# VOLTAGE_PEAK_V3.net
KiCad netlist of a schematic drawn in Altium Designer
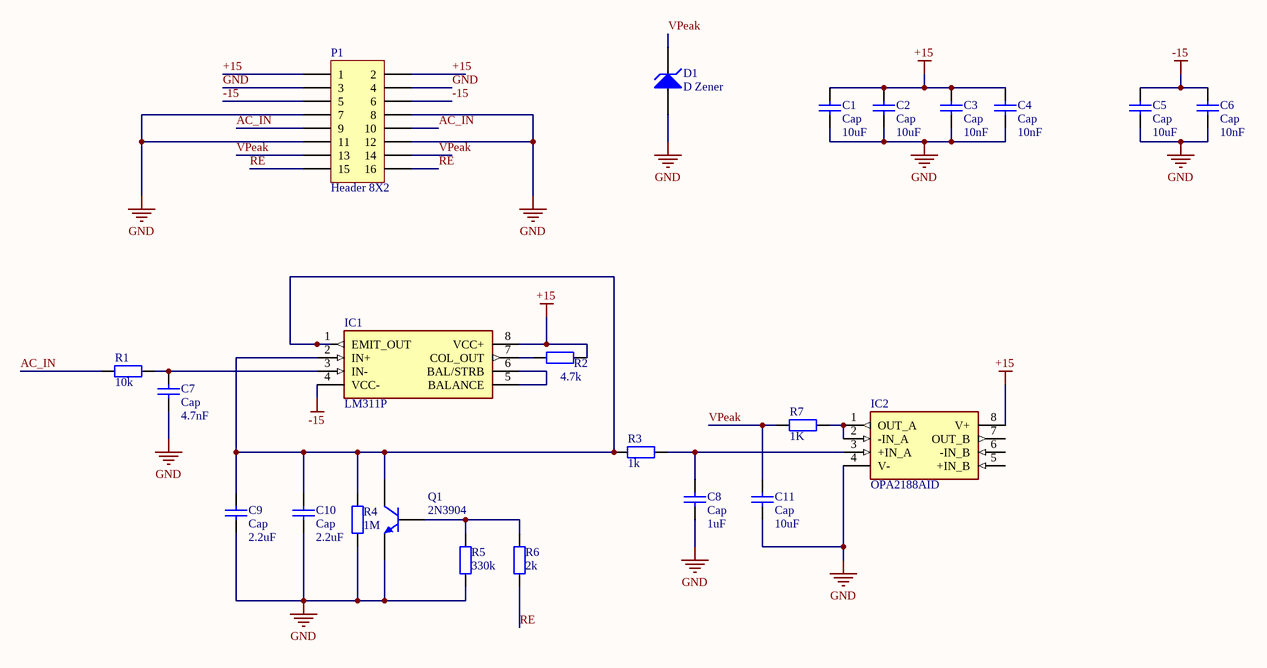
[diagram p0: VOLTAGE_PEAK_V3.SchDoc]

(export (version "E")
  (design (tool "Eeschema 10.0.6"))
  (components
    (comp (ref "C1")
      (value "Cap")
      (footprint "C0805")
      (description "Capacitor")
      (fields (field (name "ALTIUM_VALUE") "10uF") (field (name "PUBLISHER") "Altium Limited"))
      (libsource (lib "Miscellaneous Devices") (part "Cap"))
    )
    (comp (ref "C2")
      (value "Cap")
      (footprint "C0805")
      (description "Capacitor")
      (fields (field (name "ALTIUM_VALUE") "10uF") (field (name "PUBLISHER") "Altium Limited"))
      (libsource (lib "Miscellaneous Devices") (part "Cap"))
    )
    (comp (ref "C3")
      (value "Cap")
      (footprint "1608[0603]")
      (description "Capacitor")
      (fields (field (name "ALTIUM_VALUE") "10nF") (field (name "PUBLISHER") "Altium Limited"))
      (libsource (lib "Miscellaneous Devices") (part "Cap"))
    )
    (comp (ref "C4")
      (value "Cap")
      (footprint "1608[0603]")
      (description "Capacitor")
      (fields (field (name "ALTIUM_VALUE") "10nF") (field (name "PUBLISHER") "Altium Limited"))
      (libsource (lib "Miscellaneous Devices") (part "Cap"))
    )
    (comp (ref "C5")
      (value "Cap")
      (footprint "C0805")
      (description "Capacitor")
      (fields (field (name "ALTIUM_VALUE") "10uF") (field (name "PUBLISHER") "Altium Limited"))
      (libsource (lib "Miscellaneous Devices") (part "Cap"))
    )
    (comp (ref "C6")
      (value "Cap")
      (footprint "1608[0603]")
      (description "Capacitor")
      (fields (field (name "ALTIUM_VALUE") "10nF") (field (name "PUBLISHER") "Altium Limited"))
      (libsource (lib "Miscellaneous Devices") (part "Cap"))
    )
    (comp (ref "C7")
      (value "Cap")
      (footprint "1608[0603]")
      (description "Capacitor")
      (fields (field (name "ALTIUM_VALUE") "4.7nF") (field (name "PUBLISHER") "Altium Limited"))
      (libsource (lib "Miscellaneous Devices") (part "Cap"))
    )
    (comp (ref "C8")
      (value "Cap")
      (footprint "C0805")
      (description "Capacitor")
      (fields (field (name "ALTIUM_VALUE") "1uF") (field (name "PUBLISHER") "Altium Limited"))
      (libsource (lib "Miscellaneous Devices") (part "Cap"))
    )
    (comp (ref "C9")
      (value "Cap")
      (footprint "C0805")
      (description "Capacitor")
      (fields (field (name "ALTIUM_VALUE") "2.2uF") (field (name "PUBLISHER") "Altium Limited"))
      (libsource (lib "Miscellaneous Devices") (part "Cap"))
    )
    (comp (ref "C10")
      (value "Cap")
      (footprint "C0805")
      (description "Capacitor")
      (fields (field (name "ALTIUM_VALUE") "2.2uF") (field (name "PUBLISHER") "Altium Limited"))
      (libsource (lib "Miscellaneous Devices") (part "Cap"))
    )
    (comp (ref "C11")
      (value "Cap")
      (footprint "C0805")
      (description "Capacitor")
      (fields (field (name "ALTIUM_VALUE") "10uF") (field (name "PUBLISHER") "Altium Limited"))
      (libsource (lib "Miscellaneous Devices") (part "Cap"))
    )
    (comp (ref "D1")
      (value "D Zener")
      (footprint "C1206")
      (description "Zener Diode")
      (fields (field (name "PUBLISHER") "Altium Limited"))
      (libsource (lib "Miscellaneous Devices") (part "D Zener"))
    )
    (comp (ref "IC1")
      (value "LM311P")
      (footprint "SamacSys:DIP794W53P254L959H508Q8N")
      (description "Integrated Circuit")
      (fields (field (name "MOUSER PART NUMBER") "595-LM311P") (field (name "RS PART NUMBER") "1218305"))
      (libsource (lib "*") (part "LM311P"))
    )
    (comp (ref "IC2")
      (value "OPA2188AID")
      (footprint "SamacSys:SOIC127P600X175-8N")
      (description "Integrated Circuit")
      (fields (field (name "MOUSER PART NUMBER") "595-OPA2188AID") (field (name "RS PART NUMBER") "9212845"))
      (libsource (lib "*") (part "OPA2188AID"))
    )
    (comp (ref "P1")
      (value "Header 8X2")
      (footprint "HDR2X8")
      (description "Header, 8-Pin, Dual row")
      (fields (field (name "PUBLISHER") "Altium Limited"))
      (libsource (lib "Miscellaneous Connectors") (part "Header 8X2"))
    )
    (comp (ref "Q1")
      (value "2N3904")
      (footprint "TO-92A")
      (description "NPN General Purpose Amplifier")
      (fields (field (name "PUBLISHER") "Altium Limited"))
      (libsource (lib "Miscellaneous Devices") (part "2N3904"))
    )
    (comp (ref "R1")
      (value "10k")
      (footprint "1608[0603]")
      (description "Resistor")
      (fields (field (name "Comment") "Res2") (field (name "PUBLISHER") "Altium Limited"))
      (libsource (lib "Miscellaneous Devices") (part "Res2"))
    )
    (comp (ref "R2")
      (value "4.7k")
      (footprint "1608[0603]")
      (description "Resistor")
      (fields (field (name "Comment") "Res2") (field (name "PUBLISHER") "Altium Limited"))
      (libsource (lib "Miscellaneous Devices") (part "Res2"))
    )
    (comp (ref "R3")
      (value "1k")
      (footprint "1608[0603]")
      (description "Resistor")
      (fields (field (name "Comment") "Res2") (field (name "PUBLISHER") "Altium Limited"))
      (libsource (lib "Miscellaneous Devices") (part "Res2"))
    )
    (comp (ref "R4")
      (value "1M")
      (footprint "1608[0603]")
      (description "Resistor")
      (fields (field (name "Comment") "Res2") (field (name "PUBLISHER") "Altium Limited"))
      (libsource (lib "") (part "Res2_1"))
    )
    (comp (ref "R5")
      (value "330k")
      (footprint "1608[0603]")
      (description "Resistor")
      (fields (field (name "Comment") "Res2") (field (name "PUBLISHER") "Altium Limited"))
      (libsource (lib "") (part "Res2_1"))
    )
    (comp (ref "R6")
      (value "2k")
      (footprint "1608[0603]")
      (description "Resistor")
      (fields (field (name "Comment") "Res2") (field (name "PUBLISHER") "Altium Limited"))
      (libsource (lib "") (part "Res2_1"))
    )
    (comp (ref "R7")
      (value "1K")
      (footprint "1608[0603]")
      (description "Resistor")
      (fields (field (name "Comment") "Res2") (field (name "PUBLISHER") "Altium Limited"))
      (libsource (lib "Miscellaneous Devices") (part "Res2"))
    )
  )
  (nets
    (net (code "1") (name "+15") (class "Default")
      (node (ref "C1") (pin "2") (pinfunction "2_2") (pintype "passive"))
      (node (ref "C2") (pin "2") (pinfunction "2_2") (pintype "passive"))
      (node (ref "C3") (pin "1") (pinfunction "1_1") (pintype "passive"))
      (node (ref "C4") (pin "1") (pinfunction "1_1") (pintype "passive"))
      (node (ref "IC1") (pin "8") (pinfunction "VCC+_8") (pintype "power_in"))
      (node (ref "IC2") (pin "8") (pinfunction "V+_8") (pintype "power_in"))
      (node (ref "P1") (pin "1") (pinfunction "1_1") (pintype "passive"))
      (node (ref "P1") (pin "2") (pinfunction "2_2") (pintype "passive"))
      (node (ref "R2") (pin "2") (pinfunction "2_2") (pintype "passive"))
    )
    (net (code "2") (name "-15") (class "Default")
      (node (ref "C5") (pin "2") (pinfunction "2_2") (pintype "passive"))
      (node (ref "C6") (pin "1") (pinfunction "1_1") (pintype "passive"))
      (node (ref "IC1") (pin "4") (pinfunction "VCC-_4") (pintype "power_in"))
      (node (ref "P1") (pin "5") (pinfunction "5_5") (pintype "passive"))
      (node (ref "P1") (pin "6") (pinfunction "6_6") (pintype "passive"))
    )
    (net (code "3") (name "/AC_IN") (class "Default")
      (node (ref "P1") (pin "10") (pinfunction "10_10") (pintype "passive"))
      (node (ref "P1") (pin "9") (pinfunction "9_9") (pintype "passive"))
      (node (ref "R1") (pin "1") (pinfunction "1_1") (pintype "passive"))
    )
    (net (code "4") (name "/RE") (class "Default")
      (node (ref "P1") (pin "15") (pinfunction "15_15") (pintype "passive"))
      (node (ref "P1") (pin "16") (pinfunction "16_16") (pintype "passive"))
      (node (ref "R6") (pin "1") (pinfunction "1_1") (pintype "passive"))
    )
    (net (code "5") (name "/VPeak") (class "Default")
      (node (ref "C11") (pin "1") (pinfunction "1_1") (pintype "passive"))
      (node (ref "D1") (pin "2") (pinfunction "K_2") (pintype "passive"))
      (node (ref "P1") (pin "13") (pinfunction "13_13") (pintype "passive"))
      (node (ref "P1") (pin "14") (pinfunction "14_14") (pintype "passive"))
      (node (ref "R7") (pin "1") (pinfunction "1_1") (pintype "passive"))
    )
    (net (code "6") (name "GND") (class "Default")
      (node (ref "C1") (pin "1") (pinfunction "1_1") (pintype "passive"))
      (node (ref "C10") (pin "2") (pinfunction "2_2") (pintype "passive"))
      (node (ref "C11") (pin "2") (pinfunction "2_2") (pintype "passive"))
      (node (ref "C2") (pin "1") (pinfunction "1_1") (pintype "passive"))
      (node (ref "C3") (pin "2") (pinfunction "2_2") (pintype "passive"))
      (node (ref "C4") (pin "2") (pinfunction "2_2") (pintype "passive"))
      (node (ref "C5") (pin "1") (pinfunction "1_1") (pintype "passive"))
      (node (ref "C6") (pin "2") (pinfunction "2_2") (pintype "passive"))
      (node (ref "C7") (pin "2") (pinfunction "2_2") (pintype "passive"))
      (node (ref "C8") (pin "2") (pinfunction "2_2") (pintype "passive"))
      (node (ref "C9") (pin "2") (pinfunction "2_2") (pintype "passive"))
      (node (ref "D1") (pin "1") (pinfunction "A_1") (pintype "passive"))
      (node (ref "IC2") (pin "4") (pinfunction "V-_4") (pintype "power_in"))
      (node (ref "P1") (pin "11") (pinfunction "11_11") (pintype "passive"))
      (node (ref "P1") (pin "12") (pinfunction "12_12") (pintype "passive"))
      (node (ref "P1") (pin "3") (pinfunction "3_3") (pintype "passive"))
      (node (ref "P1") (pin "4") (pinfunction "4_4") (pintype "passive"))
      (node (ref "P1") (pin "7") (pinfunction "7_7") (pintype "passive"))
      (node (ref "P1") (pin "8") (pinfunction "8_8") (pintype "passive"))
      (node (ref "Q1") (pin "1") (pinfunction "E_1") (pintype "passive"))
      (node (ref "R4") (pin "1") (pinfunction "1_1") (pintype "passive"))
      (node (ref "R5") (pin "1") (pinfunction "1_1") (pintype "passive"))
    )
    (net (code "7") (name "Net-(IC1-BALANCE)") (class "Default")
      (node (ref "IC1") (pin "5") (pinfunction "BALANCE_5") (pintype "passive"))
      (node (ref "IC1") (pin "6") (pinfunction "BAL/STRB_6") (pintype "passive"))
    )
    (net (code "8") (name "Net-(IC1-COL_OUT)") (class "Default")
      (node (ref "IC1") (pin "7") (pinfunction "COL_OUT_7") (pintype "output"))
      (node (ref "R2") (pin "1") (pinfunction "1_1") (pintype "passive"))
    )
    (net (code "9") (name "Net-(IC1-EMIT_OUT)") (class "Default")
      (node (ref "C10") (pin "1") (pinfunction "1_1") (pintype "passive"))
      (node (ref "C9") (pin "1") (pinfunction "1_1") (pintype "passive"))
      (node (ref "IC1") (pin "1") (pinfunction "EMIT_OUT_1") (pintype "output"))
      (node (ref "IC1") (pin "2") (pinfunction "IN+_2") (pintype "input"))
      (node (ref "Q1") (pin "3") (pinfunction "C_3") (pintype "passive"))
      (node (ref "R3") (pin "1") (pinfunction "1_1") (pintype "passive"))
      (node (ref "R4") (pin "2") (pinfunction "2_2") (pintype "passive"))
    )
    (net (code "10") (name "Net-(IC1-IN-)") (class "Default")
      (node (ref "C7") (pin "1") (pinfunction "1_1") (pintype "passive"))
      (node (ref "IC1") (pin "3") (pinfunction "IN-_3") (pintype "input"))
      (node (ref "R1") (pin "2") (pinfunction "2_2") (pintype "passive"))
    )
    (net (code "11") (name "Net-(IC2-+IN_A)") (class "Default")
      (node (ref "C8") (pin "1") (pinfunction "1_1") (pintype "passive"))
      (node (ref "IC2") (pin "3") (pinfunction "+IN_A_3") (pintype "input"))
      (node (ref "R3") (pin "2") (pinfunction "2_2") (pintype "passive"))
    )
    (net (code "12") (name "Net-(IC2--IN_A)") (class "Default")
      (node (ref "IC2") (pin "1") (pinfunction "OUT_A_1") (pintype "output"))
      (node (ref "IC2") (pin "2") (pinfunction "-IN_A_2") (pintype "input"))
      (node (ref "R7") (pin "2") (pinfunction "2_2") (pintype "passive"))
    )
    (net (code "13") (name "Net-(Q1-B)") (class "Default")
      (node (ref "Q1") (pin "2") (pinfunction "B_2") (pintype "passive"))
      (node (ref "R5") (pin "2") (pinfunction "2_2") (pintype "passive"))
      (node (ref "R6") (pin "2") (pinfunction "2_2") (pintype "passive"))
    )
    (net (code "14") (name "unconnected-(IC2-+IN_B-Pad5)") (class "Default")
      (node (ref "IC2") (pin "5") (pinfunction "+IN_B_5") (pintype "input"))
    )
    (net (code "15") (name "unconnected-(IC2--IN_B-Pad6)") (class "Default")
      (node (ref "IC2") (pin "6") (pinfunction "-IN_B_6") (pintype "input"))
    )
    (net (code "16") (name "unconnected-(IC2-OUT_B-Pad7)") (class "Default")
      (node (ref "IC2") (pin "7") (pinfunction "OUT_B_7") (pintype "output"))
    )
  )
)
